# E-39_IPS.net
KiCad netlist of a schematic drawn in Altium Designer
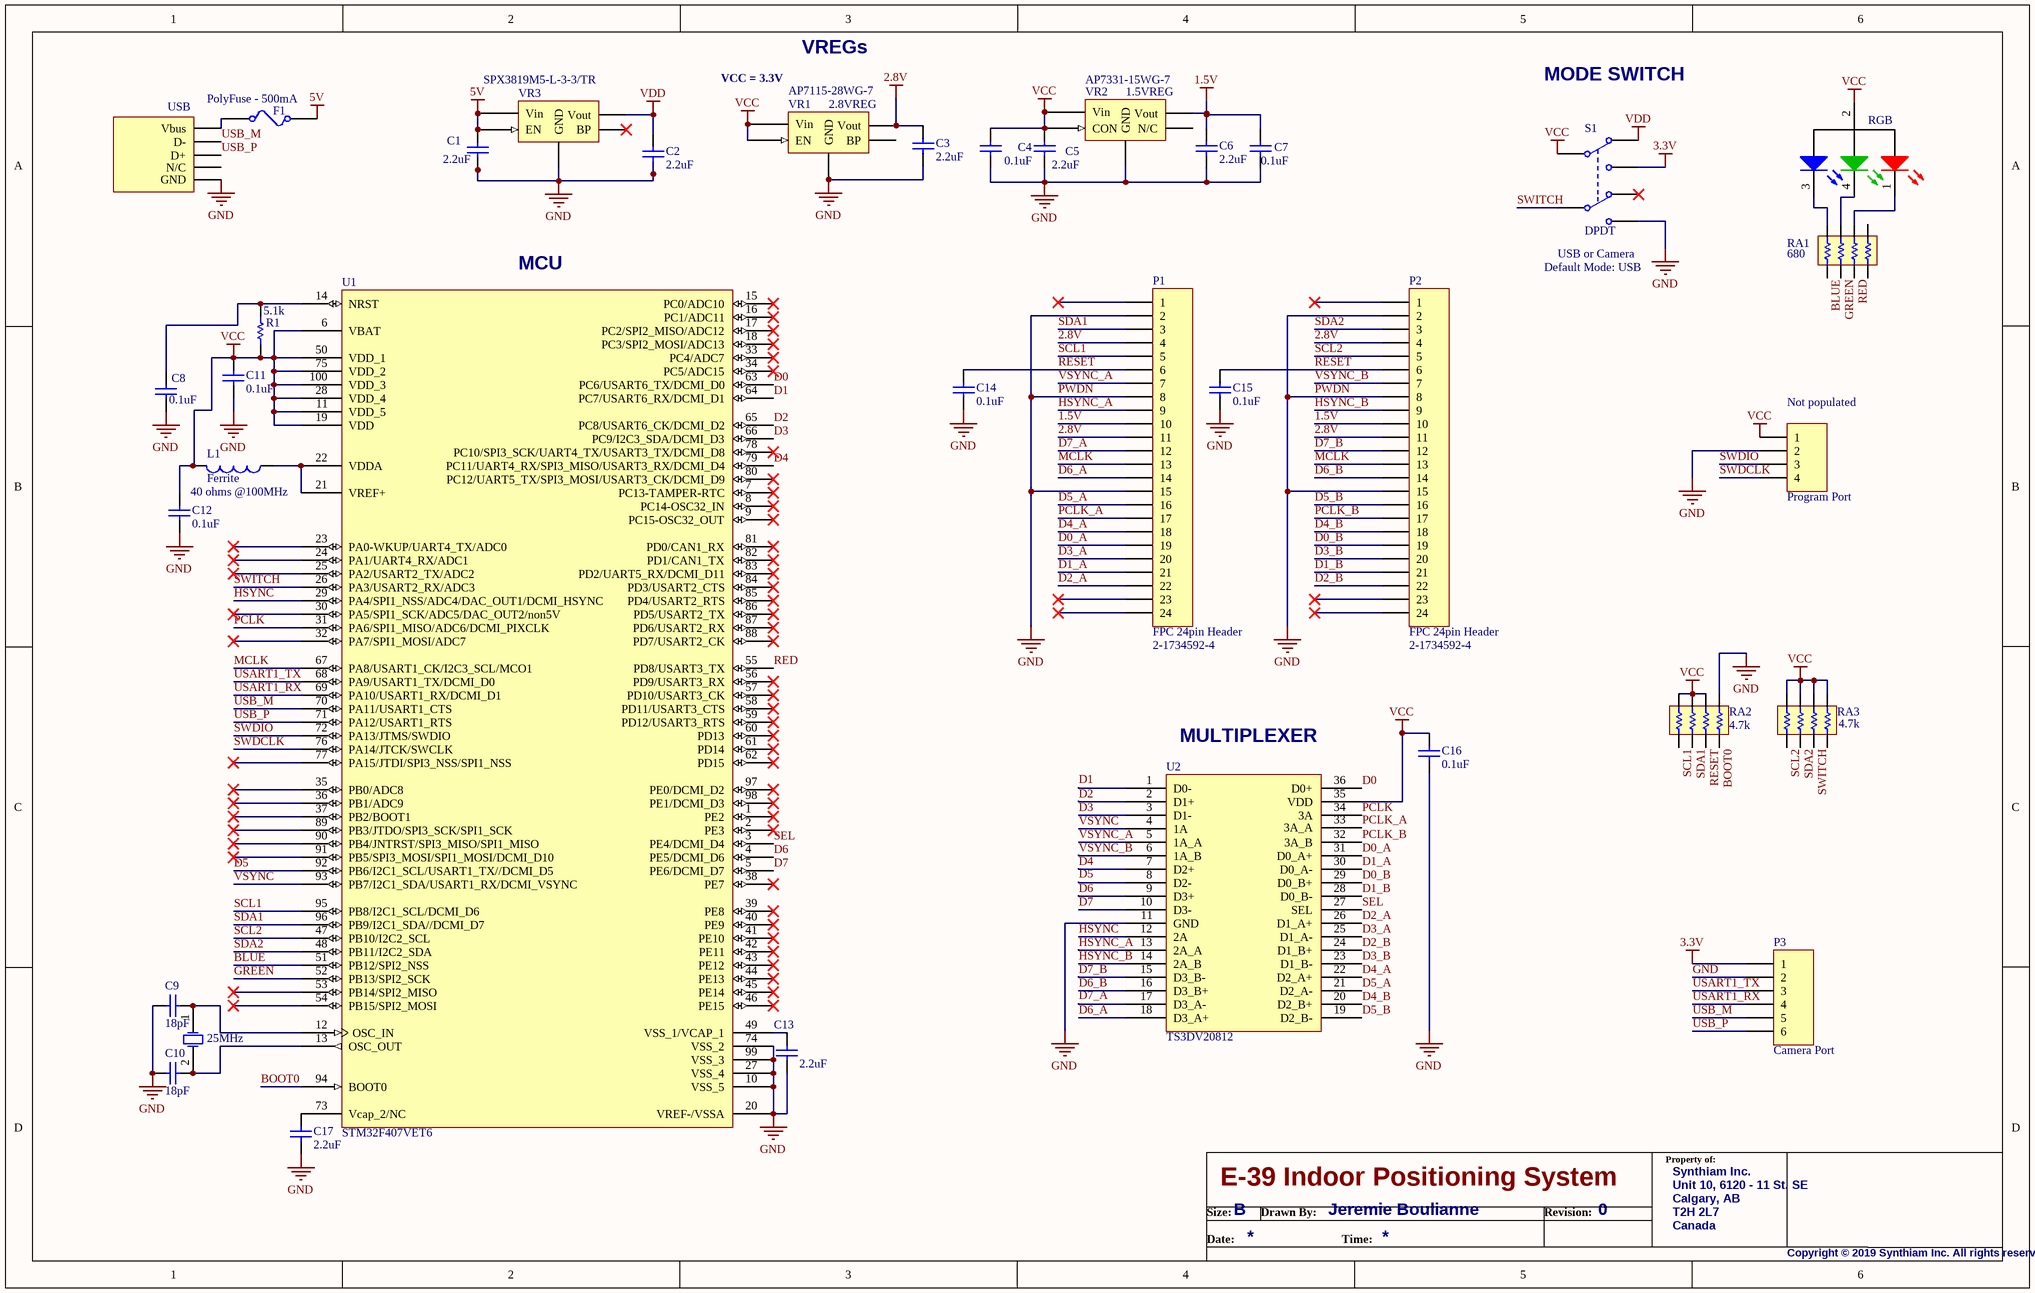
[diagram p0: E-39 IPS.SchDoc]

(export (version "E")
  (design (tool "Eeschema 10.0.6"))
  (components
    (comp (ref "25MHz")
      (value "XTAL 8MHz")
      (footprint "Crystal")
      (description "Crystal Oscillator")
      (fields (field (name "PUBLISHER") "Altium Limited"))
      (libsource (lib "SB_Discrete") (part "XTAL"))
    )
    (comp (ref "C1")
      (value "2.2uF")
      (footprint "0603 TIGHT")
      (description "Capacitor")
      (fields (field (name "Comment") "Cap") (field (name "PUBLISHER") "Altium Limited"))
      (libsource (lib "SB_Discrete") (part "Cap"))
    )
    (comp (ref "C2")
      (value "2.2uF")
      (footprint "0603 TIGHT")
      (description "Capacitor")
      (fields (field (name "Comment") "Cap") (field (name "PUBLISHER") "Altium Limited"))
      (libsource (lib "SB_Discrete") (part "Cap"))
    )
    (comp (ref "C3")
      (value "2.2uF")
      (footprint "0603 TIGHT")
      (description "Capacitor")
      (fields (field (name "PUBLISHER") "Altium Limited"))
      (libsource (lib "SB_Discrete") (part "Cap"))
    )
    (comp (ref "C4")
      (value "0.1uF")
      (footprint "0603 TIGHT")
      (description "Capacitor")
      (fields (field (name "Comment") "2.2uF") (field (name "PUBLISHER") "Altium Limited"))
      (libsource (lib "SB_Discrete") (part "Cap"))
    )
    (comp (ref "C5")
      (value "2.2uF")
      (footprint "0603 TIGHT")
      (description "Capacitor")
      (fields (field (name "PUBLISHER") "Altium Limited"))
      (libsource (lib "SB_Discrete") (part "Cap"))
    )
    (comp (ref "C6")
      (value "2.2uF")
      (footprint "0603 TIGHT")
      (description "Capacitor")
      (fields (field (name "PUBLISHER") "Altium Limited"))
      (libsource (lib "SB_Discrete") (part "Cap"))
    )
    (comp (ref "C7")
      (value "0.1uF")
      (footprint "0603 TIGHT")
      (description "Capacitor")
      (fields (field (name "Comment") "100nF") (field (name "PUBLISHER") "Altium Limited"))
      (libsource (lib "SB_Discrete") (part "Cap"))
    )
    (comp (ref "C8")
      (value "0.1uF")
      (footprint "0603 TIGHT")
      (description "Capacitor")
      (fields (field (name "Comment") "100nF") (field (name "PUBLISHER") "Altium Limited"))
      (libsource (lib "SB_Discrete") (part "Cap"))
    )
    (comp (ref "C9")
      (value "18pF")
      (footprint "0603 TIGHT")
      (description "Capacitor")
      (fields (field (name "PUBLISHER") "Altium Limited"))
      (libsource (lib "SB_Discrete") (part "Cap"))
    )
    (comp (ref "C10")
      (value "18pF")
      (footprint "0603 TIGHT")
      (description "Capacitor")
      (fields (field (name "PUBLISHER") "Altium Limited"))
      (libsource (lib "SB_Discrete") (part "Cap"))
    )
    (comp (ref "C11")
      (value "0.1uF")
      (footprint "0603 TIGHT")
      (description "Capacitor")
      (fields (field (name "Comment") "100nF") (field (name "PUBLISHER") "Altium Limited"))
      (libsource (lib "SB_Discrete") (part "Cap"))
    )
    (comp (ref "C12")
      (value "0.1uF")
      (footprint "0603 TIGHT")
      (description "Capacitor")
      (fields (field (name "Comment") "100nF") (field (name "PUBLISHER") "Altium Limited"))
      (libsource (lib "SB_Discrete") (part "Cap"))
    )
    (comp (ref "C13")
      (value "2.2uF")
      (footprint "0603 TIGHT")
      (description "Capacitor")
      (fields (field (name "PUBLISHER") "Altium Limited"))
      (libsource (lib "SB_Discrete") (part "Cap"))
    )
    (comp (ref "C14")
      (value "0.1uF")
      (footprint "0603 TIGHT")
      (description "Capacitor")
      (fields (field (name "Comment") "18pF") (field (name "PUBLISHER") "Altium Limited"))
      (libsource (lib "SB_Discrete") (part "Cap"))
    )
    (comp (ref "C15")
      (value "0.1uF")
      (footprint "0603 TIGHT")
      (description "Capacitor")
      (fields (field (name "Comment") "18pF") (field (name "PUBLISHER") "Altium Limited"))
      (libsource (lib "SB_Discrete") (part "Cap"))
    )
    (comp (ref "C16")
      (value "0.1uF")
      (footprint "0603 TIGHT")
      (description "Capacitor")
      (fields (field (name "Comment") "18pF") (field (name "PUBLISHER") "Altium Limited"))
      (libsource (lib "SB_Discrete") (part "Cap"))
    )
    (comp (ref "C17")
      (value "2.2uF")
      (footprint "0603 TIGHT")
      (description "Capacitor")
      (fields (field (name "PUBLISHER") "Altium Limited"))
      (libsource (lib "SB_Discrete") (part "Cap"))
    )
    (comp (ref "F1")
      (value "PolyFuse - 500mA")
      (footprint "1206")
      (description "PTC .50A 15VDC RESETTABLE 1812L")
      (libsource (lib "SB_Discrete") (part "PolyFuse"))
    )
    (comp (ref "L1")
      (value "Ferrite")
      (footprint "0603 tight")
      (description "Inductor")
      (fields (field (name "ALTIUM_VALUE") "40 ohms @100MHz") (field (name "PUBLISHER") "Altium Limited"))
      (libsource (lib "Miscellaneous Devices") (part "Inductor"))
    )
    (comp (ref "P1")
      (value "FPC 24pin Header")
      (footprint "FPC Connector 24pin")
      (description "Header, 24-Pin")
      (fields (field (name "PUBLISHER") "Altium Limited"))
      (libsource (lib "Miscellaneous Connectors") (part "Header 24"))
    )
    (comp (ref "P2")
      (value "FPC 24pin Header")
      (footprint "FPC Connector 24pin")
      (description "Header, 24-Pin")
      (fields (field (name "PUBLISHER") "Altium Limited"))
      (libsource (lib "Miscellaneous Connectors") (part "Header 24"))
    )
    (comp (ref "P3")
      (value "Camera Port")
      (footprint "JST-PH 6pin")
      (description "Header, 6-Pin")
      (fields (field (name "PUBLISHER") "Altium Limited"))
      (libsource (lib "Miscellaneous Connectors") (part "Header 6"))
    )
    (comp (ref "Program Port")
      (value "Not populated")
      (footprint "HDR1X4")
      (fields (field (name "PUBLISHER") "Altium Limited"))
      (libsource (lib "Miscellaneous Connectors") (part "Header 4"))
    )
    (comp (ref "R1")
      (value "5.1k")
      (footprint "0603 TIGHT")
      (description "Resistor")
      (fields (field (name "Comment") "Res1") (field (name "PUBLISHER") "Altium Limited"))
      (libsource (lib "SB_Discrete") (part "Res1"))
    )
    (comp (ref "RA1")
      (value "680")
      (footprint "Resistor Array 4")
      (libsource (lib "SB_Discrete") (part "Resistor Array 4"))
    )
    (comp (ref "RA2")
      (value "4.7k")
      (footprint "Resistor Array 4")
      (libsource (lib "SB_Discrete") (part "Resistor Array 4"))
    )
    (comp (ref "RA3")
      (value "4.7k")
      (footprint "Resistor Array 4")
      (libsource (lib "SB_Discrete") (part "Resistor Array 4"))
    )
    (comp (ref "RGB")
      (value "RGBLED-CA")
      (footprint "RGBLED-CA")
      (libsource (lib "SB_Discrete") (part "RGBLED-CA"))
    )
    (comp (ref "S1")
      (value "DPDT")
      (footprint "SWITCH DPDT SMD")
      (libsource (lib "SB_Engineered_Components") (part "SWITCH DPDT"))
    )
    (comp (ref "U1")
      (value "STM32F407VET6")
      (footprint "LQFP100_M")
      (libsource (lib "ST Microcontroller 32-Bit STM32") (part "STM32F2"))
    )
    (comp (ref "U2")
      (value "TS3DV20812")
      (footprint "QFN-36")
      (libsource (lib "SB_Engineered_Components") (part "TS3DV20812"))
    )
    (comp (ref "USB")
      (value "USB Connector")
      (footprint "MICRO USB")
      (libsource (lib "SB_Engineered_Components") (part "USB Connector"))
    )
    (comp (ref "VR1")
      (value "2.8VREG")
      (footprint "SOT-25 New")
      (libsource (lib "SB_Discrete") (part "Vreg SOT25"))
    )
    (comp (ref "VR2") (value "1.5VREG") (footprint "SOT-25 New") (libsource (lib "") (part "Vreg SOT25_1")))
    (comp (ref "VR3")
      (value "SPX3819M5-L-3-3/TR")
      (footprint "SOT-25")
      (libsource (lib "SB_Discrete") (part "Vreg SOT25"))
    )
  )
  (nets
    (net (code "4") (name "/BLUE") (class "Default")
      (node (ref "RA1") (pin "1") (pinfunction "1_1") (pintype "passive"))
      (node (ref "U1") (pin "51") (pinfunction "PB12/SPI2_NSS_51") (pintype "bidirectional"))
    )
    (net (code "5") (name "/BOOT0") (class "Default")
      (node (ref "RA2") (pin "7") (pinfunction "7_7") (pintype "passive"))
      (node (ref "U1") (pin "94") (pinfunction "BOOT0_94") (pintype "input"))
    )
    (net (code "6") (name "/D0") (class "Default")
      (node (ref "U1") (pin "63") (pinfunction "PC6/USART6_TX/DCMI_D0_63") (pintype "bidirectional"))
      (node (ref "U2") (pin "36") (pinfunction "D0+_36") (pintype "passive"))
    )
    (net (code "7") (name "/D0_A") (class "Default")
      (node (ref "P1") (pin "19") (pinfunction "19_19") (pintype "passive"))
      (node (ref "U2") (pin "31") (pinfunction "D0_A+_31") (pintype "passive"))
    )
    (net (code "8") (name "/D0_B") (class "Default")
      (node (ref "P2") (pin "19") (pinfunction "19_19") (pintype "passive"))
      (node (ref "U2") (pin "29") (pinfunction "D0_B+_29") (pintype "passive"))
    )
    (net (code "9") (name "/D1") (class "Default")
      (node (ref "U1") (pin "64") (pinfunction "PC7/USART6_RX/DCMI_D1_64") (pintype "bidirectional"))
      (node (ref "U2") (pin "1") (pinfunction "D0-_1") (pintype "passive"))
    )
    (net (code "10") (name "/D1_A") (class "Default")
      (node (ref "P1") (pin "21") (pinfunction "21_21") (pintype "passive"))
      (node (ref "U2") (pin "30") (pinfunction "D0_A-_30") (pintype "passive"))
    )
    (net (code "11") (name "/D1_B") (class "Default")
      (node (ref "P2") (pin "21") (pinfunction "21_21") (pintype "passive"))
      (node (ref "U2") (pin "28") (pinfunction "D0_B-_28") (pintype "passive"))
    )
    (net (code "12") (name "/D2") (class "Default")
      (node (ref "U1") (pin "65") (pinfunction "PC8/USART6_CK/DCMI_D2_65") (pintype "bidirectional"))
      (node (ref "U2") (pin "2") (pinfunction "D1+_2") (pintype "passive"))
    )
    (net (code "13") (name "/D2_A") (class "Default")
      (node (ref "P1") (pin "22") (pinfunction "22_22") (pintype "passive"))
      (node (ref "U2") (pin "26") (pinfunction "D1_A+_26") (pintype "passive"))
    )
    (net (code "14") (name "/D2_B") (class "Default")
      (node (ref "P2") (pin "22") (pinfunction "22_22") (pintype "passive"))
      (node (ref "U2") (pin "24") (pinfunction "D1_B+_24") (pintype "passive"))
    )
    (net (code "15") (name "/D3") (class "Default")
      (node (ref "U1") (pin "66") (pinfunction "PC9/I2C3_SDA/DCMI_D3_66") (pintype "bidirectional"))
      (node (ref "U2") (pin "3") (pinfunction "D1-_3") (pintype "passive"))
    )
    (net (code "16") (name "/D3_A") (class "Default")
      (node (ref "P1") (pin "20") (pinfunction "20_20") (pintype "passive"))
      (node (ref "U2") (pin "25") (pinfunction "D1_A-_25") (pintype "passive"))
    )
    (net (code "17") (name "/D3_B") (class "Default")
      (node (ref "P2") (pin "20") (pinfunction "20_20") (pintype "passive"))
      (node (ref "U2") (pin "23") (pinfunction "D1_B-_23") (pintype "passive"))
    )
    (net (code "18") (name "/D4") (class "Default")
      (node (ref "U1") (pin "79") (pinfunction "PC11/UART4_RX/SPI3_MISO/USART3_RX/DCMI_D4_79") (pintype "bidirectional"))
      (node (ref "U2") (pin "7") (pinfunction "D2+_7") (pintype "passive"))
    )
    (net (code "19") (name "/D4_A") (class "Default")
      (node (ref "P1") (pin "18") (pinfunction "18_18") (pintype "passive"))
      (node (ref "U2") (pin "22") (pinfunction "D2_A+_22") (pintype "passive"))
    )
    (net (code "20") (name "/D4_B") (class "Default")
      (node (ref "P2") (pin "18") (pinfunction "18_18") (pintype "passive"))
      (node (ref "U2") (pin "20") (pinfunction "D2_B+_20") (pintype "passive"))
    )
    (net (code "21") (name "/D5") (class "Default")
      (node (ref "U1") (pin "92") (pinfunction "PB6/I2C1_SCL/USART1_TX//DCMI_D5_92") (pintype "bidirectional"))
      (node (ref "U2") (pin "8") (pinfunction "D2-_8") (pintype "passive"))
    )
    (net (code "22") (name "/D5_A") (class "Default")
      (node (ref "P1") (pin "16") (pinfunction "16_16") (pintype "passive"))
      (node (ref "U2") (pin "21") (pinfunction "D2_A-_21") (pintype "passive"))
    )
    (net (code "23") (name "/D5_B") (class "Default")
      (node (ref "P2") (pin "16") (pinfunction "16_16") (pintype "passive"))
      (node (ref "U2") (pin "19") (pinfunction "D2_B-_19") (pintype "passive"))
    )
    (net (code "24") (name "/D6") (class "Default")
      (node (ref "U1") (pin "4") (pinfunction "PE5/DCMI_D6_4") (pintype "bidirectional"))
      (node (ref "U2") (pin "9") (pinfunction "D3+_9") (pintype "passive"))
    )
    (net (code "25") (name "/D6_A") (class "Default")
      (node (ref "P1") (pin "14") (pinfunction "14_14") (pintype "passive"))
      (node (ref "U2") (pin "18") (pinfunction "D3_A+_18") (pintype "passive"))
    )
    (net (code "26") (name "/D6_B") (class "Default")
      (node (ref "P2") (pin "14") (pinfunction "14_14") (pintype "passive"))
      (node (ref "U2") (pin "16") (pinfunction "D3_B+_16") (pintype "passive"))
    )
    (net (code "27") (name "/D7") (class "Default")
      (node (ref "U1") (pin "5") (pinfunction "PE6/DCMI_D7_5") (pintype "bidirectional"))
      (node (ref "U2") (pin "10") (pinfunction "D3-_10") (pintype "passive"))
    )
    (net (code "28") (name "/D7_A") (class "Default")
      (node (ref "P1") (pin "12") (pinfunction "12_12") (pintype "passive"))
      (node (ref "U2") (pin "17") (pinfunction "D3_A-_17") (pintype "passive"))
    )
    (net (code "29") (name "/D7_B") (class "Default")
      (node (ref "P2") (pin "12") (pinfunction "12_12") (pintype "passive"))
      (node (ref "U2") (pin "15") (pinfunction "D3_B-_15") (pintype "passive"))
    )
    (net (code "30") (name "/GREEN") (class "Default")
      (node (ref "RA1") (pin "3") (pinfunction "5_3") (pintype "passive"))
      (node (ref "U1") (pin "52") (pinfunction "PB13/SPI2_SCK_52") (pintype "bidirectional"))
    )
    (net (code "31") (name "/HSYNC") (class "Default")
      (node (ref "U1") (pin "29") (pinfunction "PA4/SPI1_NSS/ADC4/DAC_OUT1/DCMI_HSYNC_29") (pintype "bidirectional"))
      (node (ref "U2") (pin "12") (pinfunction "2A_12") (pintype "passive"))
    )
    (net (code "32") (name "/HSYNC_A") (class "Default")
      (node (ref "P1") (pin "9") (pinfunction "9_9") (pintype "passive"))
      (node (ref "U2") (pin "13") (pinfunction "2A_A_13") (pintype "passive"))
    )
    (net (code "33") (name "/HSYNC_B") (class "Default")
      (node (ref "P2") (pin "9") (pinfunction "9_9") (pintype "passive"))
      (node (ref "U2") (pin "14") (pinfunction "2A_B_14") (pintype "passive"))
    )
    (net (code "34") (name "/MCLK") (class "Default")
      (node (ref "P1") (pin "13") (pinfunction "13_13") (pintype "passive"))
      (node (ref "P2") (pin "13") (pinfunction "13_13") (pintype "passive"))
      (node (ref "U1") (pin "67") (pinfunction "PA8/USART1_CK/I2C3_SCL/MCO1_67") (pintype "bidirectional"))
    )
    (net (code "35") (name "/PCLK") (class "Default")
      (node (ref "U1") (pin "31") (pinfunction "PA6/SPI1_MISO/ADC6/DCMI_PIXCLK_31") (pintype "bidirectional"))
      (node (ref "U2") (pin "34") (pinfunction "3A_34") (pintype "passive"))
    )
    (net (code "36") (name "/PCLK_A") (class "Default")
      (node (ref "P1") (pin "17") (pinfunction "17_17") (pintype "passive"))
      (node (ref "U2") (pin "33") (pinfunction "3A_A_33") (pintype "passive"))
    )
    (net (code "37") (name "/PCLK_B") (class "Default")
      (node (ref "P2") (pin "17") (pinfunction "17_17") (pintype "passive"))
      (node (ref "U2") (pin "32") (pinfunction "3A_B_32") (pintype "passive"))
    )
    (net (code "38") (name "/RED") (class "Default")
      (node (ref "RA1") (pin "5") (pinfunction "3_5") (pintype "passive"))
      (node (ref "U1") (pin "55") (pinfunction "PD8/USART3_TX_55") (pintype "bidirectional"))
    )
    (net (code "39") (name "/RESET") (class "Default")
      (node (ref "C14") (pin "2") (pinfunction "2_2") (pintype "passive"))
      (node (ref "C15") (pin "2") (pinfunction "2_2") (pintype "passive"))
      (node (ref "P1") (pin "6") (pinfunction "6_6") (pintype "passive"))
      (node (ref "P2") (pin "6") (pinfunction "6_6") (pintype "passive"))
      (node (ref "RA2") (pin "5") (pinfunction "3_5") (pintype "passive"))
    )
    (net (code "40") (name "/SCL1") (class "Default")
      (node (ref "P1") (pin "5") (pinfunction "5_5") (pintype "passive"))
      (node (ref "RA2") (pin "1") (pinfunction "1_1") (pintype "passive"))
      (node (ref "U1") (pin "95") (pinfunction "PB8/I2C1_SCL/DCMI_D6_95") (pintype "bidirectional"))
    )
    (net (code "41") (name "/SCL2") (class "Default")
      (node (ref "P2") (pin "5") (pinfunction "5_5") (pintype "passive"))
      (node (ref "RA3") (pin "1") (pinfunction "1_1") (pintype "passive"))
      (node (ref "U1") (pin "47") (pinfunction "PB10/I2C2_SCL_47") (pintype "bidirectional"))
    )
    (net (code "42") (name "/SDA1") (class "Default")
      (node (ref "P1") (pin "3") (pinfunction "3_3") (pintype "passive"))
      (node (ref "RA2") (pin "3") (pinfunction "5_3") (pintype "passive"))
      (node (ref "U1") (pin "96") (pinfunction "PB9/I2C1_SDA//DCMI_D7_96") (pintype "bidirectional"))
    )
    (net (code "43") (name "/SDA2") (class "Default")
      (node (ref "P2") (pin "3") (pinfunction "3_3") (pintype "passive"))
      (node (ref "RA3") (pin "3") (pinfunction "5_3") (pintype "passive"))
      (node (ref "U1") (pin "48") (pinfunction "PB11/I2C2_SDA_48") (pintype "bidirectional"))
    )
    (net (code "44") (name "/SEL") (class "Default")
      (node (ref "U1") (pin "3") (pinfunction "PE4/DCMI_D4_3") (pintype "bidirectional"))
      (node (ref "U2") (pin "27") (pinfunction "SEL_27") (pintype "passive"))
    )
    (net (code "45") (name "/SWDCLK") (class "Default")
      (node (ref "Program Port") (pin "4") (pinfunction "4_4") (pintype "passive"))
      (node (ref "U1") (pin "76") (pinfunction "PA14/JTCK/SWCLK_76") (pintype "bidirectional"))
    )
    (net (code "46") (name "/SWDIO") (class "Default")
      (node (ref "Program Port") (pin "3") (pinfunction "3_3") (pintype "passive"))
      (node (ref "U1") (pin "72") (pinfunction "PA13/JTMS/SWDIO_72") (pintype "bidirectional"))
    )
    (net (code "47") (name "/SWITCH") (class "Default")
      (node (ref "RA3") (pin "5") (pinfunction "3_5") (pintype "passive"))
      (node (ref "S1") (pin "5") (pinfunction "COMMON2_5") (pintype "passive"))
      (node (ref "U1") (pin "26") (pinfunction "PA3/USART2_RX/ADC3_26") (pintype "bidirectional"))
    )
    (net (code "48") (name "/USART1_RX") (class "Default")
      (node (ref "P3") (pin "4") (pinfunction "4_4") (pintype "passive"))
      (node (ref "U1") (pin "69") (pinfunction "PA10/USART1_RX/DCMI_D1_69") (pintype "bidirectional"))
    )
    (net (code "49") (name "/USART1_TX") (class "Default")
      (node (ref "P3") (pin "3") (pinfunction "3_3") (pintype "passive"))
      (node (ref "U1") (pin "68") (pinfunction "PA9/USART1_TX/DCMI_D0_68") (pintype "bidirectional"))
    )
    (net (code "50") (name "/USB_M") (class "Default")
      (node (ref "P3") (pin "5") (pinfunction "5_5") (pintype "passive"))
      (node (ref "U1") (pin "70") (pinfunction "PA11/USART1_CTS_70") (pintype "bidirectional"))
      (node (ref "USB") (pin "2") (pinfunction "D-_2") (pintype "passive"))
    )
    (net (code "51") (name "/USB_P") (class "Default")
      (node (ref "P3") (pin "6") (pinfunction "6_6") (pintype "passive"))
      (node (ref "U1") (pin "71") (pinfunction "PA12/USART1_RTS_71") (pintype "bidirectional"))
      (node (ref "USB") (pin "3") (pinfunction "D+_3") (pintype "passive"))
    )
    (net (code "52") (name "/VSYNC") (class "Default")
      (node (ref "U1") (pin "93") (pinfunction "PB7/I2C1_SDA/USART1_RX/DCMI_VSYNC_93") (pintype "bidirectional"))
      (node (ref "U2") (pin "4") (pinfunction "1A_4") (pintype "passive"))
    )
    (net (code "53") (name "/VSYNC_A") (class "Default")
      (node (ref "P1") (pin "7") (pinfunction "7_7") (pintype "passive"))
      (node (ref "U2") (pin "5") (pinfunction "1A_A_5") (pintype "passive"))
    )
    (net (code "54") (name "/VSYNC_B") (class "Default")
      (node (ref "P2") (pin "7") (pinfunction "7_7") (pintype "passive"))
      (node (ref "U2") (pin "6") (pinfunction "1A_B_6") (pintype "passive"))
    )
    (net (code "55") (name "1.5V") (class "Default")
      (node (ref "C6") (pin "1") (pinfunction "1_1") (pintype "passive"))
      (node (ref "C7") (pin "1") (pinfunction "1_1") (pintype "passive"))
      (node (ref "P1") (pin "10") (pinfunction "10_10") (pintype "passive"))
      (node (ref "P2") (pin "10") (pinfunction "10_10") (pintype "passive"))
      (node (ref "VR2") (pin "2") (pinfunction "Vout_2") (pintype "passive"))
    )
    (net (code "56") (name "2.8V") (class "Default")
      (node (ref "C3") (pin "1") (pinfunction "1_1") (pintype "passive"))
      (node (ref "P1") (pin "11") (pinfunction "11_11") (pintype "passive"))
      (node (ref "P1") (pin "4") (pinfunction "4_4") (pintype "passive"))
      (node (ref "P2") (pin "11") (pinfunction "11_11") (pintype "passive"))
      (node (ref "P2") (pin "4") (pinfunction "4_4") (pintype "passive"))
      (node (ref "VR1") (pin "2") (pinfunction "Vout_2") (pintype "passive"))
    )
    (net (code "57") (name "3.3V") (class "Default")
      (node (ref "P3") (pin "1") (pinfunction "1_1") (pintype "passive"))
      (node (ref "S1") (pin "3") (pinfunction "NO1_3") (pintype "passive"))
    )
    (net (code "58") (name "5V") (class "Default")
      (node (ref "C1") (pin "1") (pinfunction "1_1") (pintype "passive"))
      (node (ref "F1") (pin "1") (pinfunction "1_1") (pintype "passive"))
      (node (ref "VR3") (pin "4") (pinfunction "EN_4") (pintype "input"))
      (node (ref "VR3") (pin "5") (pinfunction "Vin_5") (pintype "passive"))
    )
    (net (code "59") (name "GND") (class "Default")
      (node (ref "C1") (pin "2") (pinfunction "2_2") (pintype "passive"))
      (node (ref "C10") (pin "2") (pinfunction "2_2") (pintype "passive"))
      (node (ref "C11") (pin "2") (pinfunction "2_2") (pintype "passive"))
      (node (ref "C12") (pin "1") (pinfunction "1_1") (pintype "passive"))
      (node (ref "C13") (pin "2") (pinfunction "2_2") (pintype "passive"))
      (node (ref "C14") (pin "1") (pinfunction "1_1") (pintype "passive"))
      (node (ref "C15") (pin "1") (pinfunction "1_1") (pintype "passive"))
      (node (ref "C16") (pin "1") (pinfunction "1_1") (pintype "passive"))
      (node (ref "C17") (pin "2") (pinfunction "2_2") (pintype "passive"))
      (node (ref "C2") (pin "2") (pinfunction "2_2") (pintype "passive"))
      (node (ref "C3") (pin "2") (pinfunction "2_2") (pintype "passive"))
      (node (ref "C4") (pin "2") (pinfunction "2_2") (pintype "passive"))
      (node (ref "C5") (pin "2") (pinfunction "2_2") (pintype "passive"))
      (node (ref "C6") (pin "2") (pinfunction "2_2") (pintype "passive"))
      (node (ref "C7") (pin "2") (pinfunction "2_2") (pintype "passive"))
      (node (ref "C8") (pin "2") (pinfunction "2_2") (pintype "passive"))
      (node (ref "C9") (pin "2") (pinfunction "2_2") (pintype "passive"))
      (node (ref "P1") (pin "15") (pinfunction "15_15") (pintype "passive"))
      (node (ref "P1") (pin "2") (pinfunction "2_2") (pintype "passive"))
      (node (ref "P1") (pin "8") (pinfunction "8_8") (pintype "passive"))
      (node (ref "P2") (pin "15") (pinfunction "15_15") (pintype "passive"))
      (node (ref "P2") (pin "2") (pinfunction "2_2") (pintype "passive"))
      (node (ref "P2") (pin "8") (pinfunction "8_8") (pintype "passive"))
      (node (ref "P3") (pin "2") (pinfunction "2_2") (pintype "passive"))
      (node (ref "Program Port") (pin "2") (pinfunction "2_2") (pintype "passive"))
      (node (ref "RA2") (pin "8") (pinfunction "8_8") (pintype "passive"))
      (node (ref "S1") (pin "6") (pinfunction "NO2_6") (pintype "passive"))
      (node (ref "U1") (pin "10") (pinfunction "VSS_5_10") (pintype "power_in"))
      (node (ref "U1") (pin "20") (pinfunction "VREF-/VSSA_20") (pintype "power_in"))
      (node (ref "U1") (pin "27") (pinfunction "VSS_4_27") (pintype "power_in"))
      (node (ref "U1") (pin "74") (pinfunction "VSS_2_74") (pintype "power_in"))
      (node (ref "U1") (pin "99") (pinfunction "VSS_3_99") (pintype "power_in"))
      (node (ref "U2") (pin "11") (pinfunction "GND_11") (pintype "passive"))
      (node (ref "USB") (pin "5") (pinfunction "GND_5") (pintype "passive"))
      (node (ref "VR1") (pin "3") (pinfunction "GND_3") (pintype "passive"))
      (node (ref "VR2") (pin "3") (pinfunction "GND_3") (pintype "passive"))
      (node (ref "VR3") (pin "3") (pinfunction "GND_3") (pintype "passive"))
    )
    (net (code "60") (name "Net-(25MHz-OSC1)") (class "Default")
      (node (ref "25MHz") (pin "1") (pinfunction "OSC1_1") (pintype "passive"))
      (node (ref "C9") (pin "1") (pinfunction "1_1") (pintype "passive"))
      (node (ref "U1") (pin "12") (pinfunction "OSC_IN_12") (pintype "input"))
    )
    (net (code "61") (name "Net-(25MHz-OSC2)") (class "Default")
      (node (ref "25MHz") (pin "2") (pinfunction "OSC2_2") (pintype "passive"))
      (node (ref "C10") (pin "1") (pinfunction "1_1") (pintype "passive"))
      (node (ref "U1") (pin "13") (pinfunction "OSC_OUT_13") (pintype "output"))
    )
    (net (code "62") (name "Net-(RA1-4)") (class "Default")
      (node (ref "RA1") (pin "6") (pinfunction "4_6") (pintype "passive"))
      (node (ref "RGB") (pin "1") (pinfunction "1_1") (pintype "passive"))
    )
    (net (code "63") (name "Net-(RA1-6)") (class "Default")
      (node (ref "RA1") (pin "4") (pinfunction "6_4") (pintype "passive"))
      (node (ref "RGB") (pin "4") (pinfunction "4_4") (pintype "passive"))
    )
    (net (code "64") (name "Net-(RA1-Pad2)") (class "Default")
      (node (ref "RA1") (pin "2") (pinfunction "2_2") (pintype "passive"))
      (node (ref "RGB") (pin "3") (pinfunction "3_3") (pintype "passive"))
    )
    (net (code "65") (name "Net-(U1-NRST)") (class "Default")
      (node (ref "C8") (pin "1") (pinfunction "1_1") (pintype "passive"))
      (node (ref "R1") (pin "1") (pinfunction "1_1") (pintype "passive"))
      (node (ref "U1") (pin "14") (pinfunction "NRST_14") (pintype "bidirectional"))
    )
    (net (code "66") (name "Net-(U1-VDDA)") (class "Default")
      (node (ref "L1") (pin "1") (pinfunction "1_1") (pintype "passive"))
      (node (ref "U1") (pin "21") (pinfunction "VREF+_21") (pintype "power_in"))
      (node (ref "U1") (pin "22") (pinfunction "VDDA_22") (pintype "power_in"))
    )
    (net (code "67") (name "Net-(U1-VSS_1{slash}VCAP_1)") (class "Default")
      (node (ref "C13") (pin "1") (pinfunction "1_1") (pintype "passive"))
      (node (ref "U1") (pin "49") (pinfunction "VSS_1/VCAP_1_49") (pintype "power_in"))
    )
    (net (code "68") (name "Net-(U1-Vcap_2{slash}NC)") (class "Default")
      (node (ref "C17") (pin "1") (pinfunction "1_1") (pintype "passive"))
      (node (ref "U1") (pin "73") (pinfunction "Vcap_2/NC_73") (pintype "passive"))
    )
    (net (code "69") (name "Net-(USB-Vbus)") (class "Default")
      (node (ref "F1") (pin "2") (pinfunction "2_2") (pintype "passive"))
      (node (ref "USB") (pin "1") (pinfunction "Vbus_1") (pintype "passive"))
    )
    (net (code "70") (name "VCC") (class "Default")
      (node (ref "C11") (pin "1") (pinfunction "1_1") (pintype "passive"))
      (node (ref "C12") (pin "2") (pinfunction "2_2") (pintype "passive"))
      (node (ref "C16") (pin "2") (pinfunction "2_2") (pintype "passive"))
      (node (ref "C4") (pin "1") (pinfunction "1_1") (pintype "passive"))
      (node (ref "C5") (pin "1") (pinfunction "1_1") (pintype "passive"))
      (node (ref "L1") (pin "2") (pinfunction "2_2") (pintype "passive"))
      (node (ref "Program Port") (pin "1") (pinfunction "1_1") (pintype "passive"))
      (node (ref "R1") (pin "2") (pinfunction "2_2") (pintype "passive"))
      (node (ref "RA2") (pin "2") (pinfunction "2_2") (pintype "passive"))
      (node (ref "RA2") (pin "4") (pinfunction "6_4") (pintype "passive"))
      (node (ref "RA2") (pin "6") (pinfunction "4_6") (pintype "passive"))
      (node (ref "RA3") (pin "2") (pinfunction "2_2") (pintype "passive"))
      (node (ref "RA3") (pin "4") (pinfunction "6_4") (pintype "passive"))
      (node (ref "RA3") (pin "6") (pinfunction "4_6") (pintype "passive"))
      (node (ref "RA3") (pin "8") (pinfunction "8_8") (pintype "passive"))
      (node (ref "RGB") (pin "2") (pinfunction "2_2") (pintype "passive"))
      (node (ref "S1") (pin "2") (pinfunction "COMMON1_2") (pintype "passive"))
      (node (ref "U1") (pin "100") (pinfunction "VDD_3_100") (pintype "power_in"))
      (node (ref "U1") (pin "11") (pinfunction "VDD_5_11") (pintype "power_in"))
      (node (ref "U1") (pin "19") (pinfunction "VDD_19") (pintype "power_in"))
      (node (ref "U1") (pin "28") (pinfunction "VDD_4_28") (pintype "power_in"))
      (node (ref "U1") (pin "50") (pinfunction "VDD_1_50") (pintype "power_in"))
      (node (ref "U1") (pin "6") (pinfunction "VBAT_6") (pintype "power_in"))
      (node (ref "U1") (pin "75") (pinfunction "VDD_2_75") (pintype "power_in"))
      (node (ref "U2") (pin "35") (pinfunction "VDD_35") (pintype "passive"))
      (node (ref "VR1") (pin "4") (pinfunction "EN_4") (pintype "input"))
      (node (ref "VR1") (pin "5") (pinfunction "Vin_5") (pintype "passive"))
      (node (ref "VR2") (pin "4") (pinfunction "CON_4") (pintype "input"))
      (node (ref "VR2") (pin "5") (pinfunction "Vin_5") (pintype "passive"))
    )
    (net (code "71") (name "VDD") (class "Default")
      (node (ref "C2") (pin "1") (pinfunction "1_1") (pintype "passive"))
      (node (ref "S1") (pin "1") (pinfunction "NC1_1") (pintype "passive"))
      (node (ref "VR3") (pin "2") (pinfunction "Vout_2") (pintype "passive"))
    )
    (net (code "72") (name "unconnected-(P1-Pad1)") (class "Default")
      (node (ref "P1") (pin "1") (pinfunction "1_1") (pintype "passive+no_connect"))
    )
    (net (code "73") (name "unconnected-(P1-Pad23)") (class "Default")
      (node (ref "P1") (pin "23") (pinfunction "23_23") (pintype "passive+no_connect"))
    )
    (net (code "74") (name "unconnected-(P1-Pad24)") (class "Default")
      (node (ref "P1") (pin "24") (pinfunction "24_24") (pintype "passive+no_connect"))
    )
    (net (code "75") (name "unconnected-(P2-Pad1)") (class "Default")
      (node (ref "P2") (pin "1") (pinfunction "1_1") (pintype "passive+no_connect"))
    )
    (net (code "76") (name "unconnected-(P2-Pad23)") (class "Default")
      (node (ref "P2") (pin "23") (pinfunction "23_23") (pintype "passive+no_connect"))
    )
    (net (code "77") (name "unconnected-(P2-Pad24)") (class "Default")
      (node (ref "P2") (pin "24") (pinfunction "24_24") (pintype "passive+no_connect"))
    )
    (net (code "78") (name "unconnected-(RA1-Pad7)") (class "Default")
      (node (ref "RA1") (pin "7") (pinfunction "7_7") (pintype "passive"))
    )
    (net (code "79") (name "unconnected-(RA1-Pad8)") (class "Default")
      (node (ref "RA1") (pin "8") (pinfunction "8_8") (pintype "passive"))
    )
    (net (code "80") (name "unconnected-(RA3-Pad7)") (class "Default")
      (node (ref "RA3") (pin "7") (pinfunction "7_7") (pintype "passive"))
    )
    (net (code "81") (name "unconnected-(RGB-A-Pad1)") (class "Default")
      (node (ref "RGB") (pin "1") (pinfunction "A_1") (pintype "passive"))
    )
    (net (code "82") (name "unconnected-(RGB-A-Pad1)_1") (class "Default")
      (node (ref "RGB") (pin "1") (pinfunction "A_1") (pintype "passive"))
    )
    (net (code "83") (name "unconnected-(RGB-A-Pad1)_2") (class "Default")
      (node (ref "RGB") (pin "1") (pinfunction "A_1") (pintype "passive"))
    )
    (net (code "84") (name "unconnected-(S1-NC2-Pad4)") (class "Default")
      (node (ref "S1") (pin "4") (pinfunction "NC2_4") (pintype "passive+no_connect"))
    )
    (net (code "85") (name "unconnected-(U1-PA0-WKUP{slash}UART4_TX{slash}ADC0-Pad23)") (class "Default")
      (node (ref "U1") (pin "23") (pinfunction "PA0-WKUP/UART4_TX/ADC0_23") (pintype "bidirectional+no_connect"))
    )
    (net (code "86") (name "unconnected-(U1-PA1{slash}UART4_RX{slash}ADC1-Pad24)") (class "Default")
      (node (ref "U1") (pin "24") (pinfunction "PA1/UART4_RX/ADC1_24") (pintype "bidirectional+no_connect"))
    )
    (net (code "87") (name "unconnected-(U1-PA2{slash}USART2_TX{slash}ADC2-Pad25)") (class "Default")
      (node (ref "U1") (pin "25") (pinfunction "PA2/USART2_TX/ADC2_25") (pintype "bidirectional+no_connect"))
    )
    (net (code "88") (name "unconnected-(U1-PA5{slash}SPI1_SCK{slash}ADC5{slash}DAC_OUT2{slash}non5V-Pad30)") (class "Default")
      (node (ref "U1") (pin "30") (pinfunction "PA5/SPI1_SCK/ADC5/DAC_OUT2/non5V_30") (pintype "bidirectional+no_connect"))
    )
    (net (code "89") (name "unconnected-(U1-PA7{slash}SPI1_MOSI{slash}ADC7-Pad32)") (class "Default")
      (node (ref "U1") (pin "32") (pinfunction "PA7/SPI1_MOSI/ADC7_32") (pintype "bidirectional+no_connect"))
    )
    (net (code "90") (name "unconnected-(U1-PA15{slash}JTDI{slash}SPI3_NSS{slash}SPI1_NSS-Pad77)") (class "Default")
      (node (ref "U1") (pin "77") (pinfunction "PA15/JTDI/SPI3_NSS/SPI1_NSS_77") (pintype "bidirectional+no_connect"))
    )
    (net (code "91") (name "unconnected-(U1-PB0{slash}ADC8-Pad35)") (class "Default")
      (node (ref "U1") (pin "35") (pinfunction "PB0/ADC8_35") (pintype "bidirectional+no_connect"))
    )
    (net (code "92") (name "unconnected-(U1-PB1{slash}ADC9-Pad36)") (class "Default")
      (node (ref "U1") (pin "36") (pinfunction "PB1/ADC9_36") (pintype "bidirectional+no_connect"))
    )
    (net (code "93") (name "unconnected-(U1-PB2{slash}BOOT1-Pad37)") (class "Default")
      (node (ref "U1") (pin "37") (pinfunction "PB2/BOOT1_37") (pintype "bidirectional+no_connect"))
    )
    (net (code "94") (name "unconnected-(U1-PB3{slash}JTDO{slash}SPI3_SCK{slash}SPI1_SCK-Pad89)") (class "Default")
      (node (ref "U1") (pin "89") (pinfunction "PB3/JTDO/SPI3_SCK/SPI1_SCK_89") (pintype "bidirectional+no_connect"))
    )
    (net (code "95") (name "unconnected-(U1-PB4{slash}JNTRST{slash}SPI3_MISO{slash}SPI1_MISO-Pad90)") (class "Default")
      (node (ref "U1") (pin "90") (pinfunction "PB4/JNTRST/SPI3_MISO/SPI1_MISO_90") (pintype "bidirectional+no_connect"))
    )
    (net (code "96") (name "unconnected-(U1-PB5{slash}SPI3_MOSI{slash}SPI1_MOSI{slash}DCMI_D10-Pad91)") (class "Default")
      (node (ref "U1") (pin "91") (pinfunction "PB5/SPI3_MOSI/SPI1_MOSI/DCMI_D10_91") (pintype "bidirectional+no_connect"))
    )
    (net (code "97") (name "unconnected-(U1-PB14{slash}SPI2_MISO-Pad53)") (class "Default")
      (node (ref "U1") (pin "53") (pinfunction "PB14/SPI2_MISO_53") (pintype "bidirectional+no_connect"))
    )
    (net (code "98") (name "unconnected-(U1-PB15{slash}SPI2_MOSI-Pad54)") (class "Default")
      (node (ref "U1") (pin "54") (pinfunction "PB15/SPI2_MOSI_54") (pintype "bidirectional+no_connect"))
    )
    (net (code "99") (name "unconnected-(U1-PC0{slash}ADC10-Pad15)") (class "Default")
      (node (ref "U1") (pin "15") (pinfunction "PC0/ADC10_15") (pintype "bidirectional+no_connect"))
    )
    (net (code "100") (name "unconnected-(U1-PC1{slash}ADC11-Pad16)") (class "Default")
      (node (ref "U1") (pin "16") (pinfunction "PC1/ADC11_16") (pintype "bidirectional+no_connect"))
    )
    (net (code "101") (name "unconnected-(U1-PC2{slash}SPI2_MISO{slash}ADC12-Pad17)") (class "Default")
      (node (ref "U1") (pin "17") (pinfunction "PC2/SPI2_MISO/ADC12_17") (pintype "bidirectional+no_connect"))
    )
    (net (code "102") (name "unconnected-(U1-PC3{slash}SPI2_MOSI{slash}ADC13-Pad18)") (class "Default")
      (node (ref "U1") (pin "18") (pinfunction "PC3/SPI2_MOSI/ADC13_18") (pintype "bidirectional+no_connect"))
    )
    (net (code "103") (name "unconnected-(U1-PC4{slash}ADC7-Pad33)") (class "Default")
      (node (ref "U1") (pin "33") (pinfunction "PC4/ADC7_33") (pintype "bidirectional+no_connect"))
    )
    (net (code "104") (name "unconnected-(U1-PC5{slash}ADC15-Pad34)") (class "Default")
      (node (ref "U1") (pin "34") (pinfunction "PC5/ADC15_34") (pintype "bidirectional+no_connect"))
    )
    (net (code "105") (name "unconnected-(U1-PC10{slash}SPI3_SCK{slash}UART4_TX{slash}USART3_TX{slash}DCMI_D8-Pad78)") (class "Default")
      (node (ref "U1") (pin "78") (pinfunction "PC10/SPI3_SCK/UART4_TX/USART3_TX/DCMI_D8_78") (pintype "bidirectional+no_connect"))
    )
    (net (code "106") (name "unconnected-(U1-PC12{slash}UART5_TX{slash}SPI3_MOSI{slash}USART3_CK{slash}DCMI_D9-Pad80)") (class "Default")
      (node (ref "U1") (pin "80") (pinfunction "PC12/UART5_TX/SPI3_MOSI/USART3_CK/DCMI_D9_80") (pintype "bidirectional+no_connect"))
    )
    (net (code "107") (name "unconnected-(U1-PC13-TAMPER-RTC-Pad7)") (class "Default")
      (node (ref "U1") (pin "7") (pinfunction "PC13-TAMPER-RTC_7") (pintype "bidirectional+no_connect"))
    )
    (net (code "108") (name "unconnected-(U1-PC14-OSC32_IN-Pad8)") (class "Default")
      (node (ref "U1") (pin "8") (pinfunction "PC14-OSC32_IN_8") (pintype "bidirectional+no_connect"))
    )
    (net (code "109") (name "unconnected-(U1-PC15-OSC32_OUT-Pad9)") (class "Default")
      (node (ref "U1") (pin "9") (pinfunction "PC15-OSC32_OUT_9") (pintype "bidirectional+no_connect"))
    )
    (net (code "110") (name "unconnected-(U1-PD0{slash}CAN1_RX-Pad81)") (class "Default")
      (node (ref "U1") (pin "81") (pinfunction "PD0/CAN1_RX_81") (pintype "bidirectional+no_connect"))
    )
    (net (code "111") (name "unconnected-(U1-PD1{slash}CAN1_TX-Pad82)") (class "Default")
      (node (ref "U1") (pin "82") (pinfunction "PD1/CAN1_TX_82") (pintype "bidirectional+no_connect"))
    )
    (net (code "112") (name "unconnected-(U1-PD2{slash}UART5_RX{slash}DCMI_D11-Pad83)") (class "Default")
      (node (ref "U1") (pin "83") (pinfunction "PD2/UART5_RX/DCMI_D11_83") (pintype "bidirectional+no_connect"))
    )
    (net (code "113") (name "unconnected-(U1-PD3{slash}USART2_CTS-Pad84)") (class "Default")
      (node (ref "U1") (pin "84") (pinfunction "PD3/USART2_CTS_84") (pintype "bidirectional+no_connect"))
    )
    (net (code "114") (name "unconnected-(U1-PD4{slash}USART2_RTS-Pad85)") (class "Default")
      (node (ref "U1") (pin "85") (pinfunction "PD4/USART2_RTS_85") (pintype "bidirectional+no_connect"))
    )
    (net (code "115") (name "unconnected-(U1-PD5{slash}USART2_TX-Pad86)") (class "Default")
      (node (ref "U1") (pin "86") (pinfunction "PD5/USART2_TX_86") (pintype "bidirectional+no_connect"))
    )
    (net (code "116") (name "unconnected-(U1-PD6{slash}USART2_RX-Pad87)") (class "Default")
      (node (ref "U1") (pin "87") (pinfunction "PD6/USART2_RX_87") (pintype "bidirectional+no_connect"))
    )
    (net (code "117") (name "unconnected-(U1-PD7{slash}USART2_CK-Pad88)") (class "Default")
      (node (ref "U1") (pin "88") (pinfunction "PD7/USART2_CK_88") (pintype "bidirectional+no_connect"))
    )
    (net (code "118") (name "unconnected-(U1-PD9{slash}USART3_RX-Pad56)") (class "Default")
      (node (ref "U1") (pin "56") (pinfunction "PD9/USART3_RX_56") (pintype "bidirectional+no_connect"))
    )
    (net (code "119") (name "unconnected-(U1-PD10{slash}USART3_CK-Pad57)") (class "Default")
      (node (ref "U1") (pin "57") (pinfunction "PD10/USART3_CK_57") (pintype "bidirectional+no_connect"))
    )
    (net (code "120") (name "unconnected-(U1-PD11{slash}USART3_CTS-Pad58)") (class "Default")
      (node (ref "U1") (pin "58") (pinfunction "PD11/USART3_CTS_58") (pintype "bidirectional+no_connect"))
    )
    (net (code "121") (name "unconnected-(U1-PD12{slash}USART3_RTS-Pad59)") (class "Default")
      (node (ref "U1") (pin "59") (pinfunction "PD12/USART3_RTS_59") (pintype "bidirectional+no_connect"))
    )
    (net (code "122") (name "unconnected-(U1-PD13-Pad60)") (class "Default")
      (node (ref "U1") (pin "60") (pinfunction "PD13_60") (pintype "bidirectional+no_connect"))
    )
    (net (code "123") (name "unconnected-(U1-PD14-Pad61)") (class "Default")
      (node (ref "U1") (pin "61") (pinfunction "PD14_61") (pintype "bidirectional+no_connect"))
    )
    (net (code "124") (name "unconnected-(U1-PD15-Pad62)") (class "Default")
      (node (ref "U1") (pin "62") (pinfunction "PD15_62") (pintype "bidirectional+no_connect"))
    )
    (net (code "125") (name "unconnected-(U1-PE0{slash}DCMI_D2-Pad97)") (class "Default")
      (node (ref "U1") (pin "97") (pinfunction "PE0/DCMI_D2_97") (pintype "bidirectional+no_connect"))
    )
    (net (code "126") (name "unconnected-(U1-PE1{slash}DCMI_D3-Pad98)") (class "Default")
      (node (ref "U1") (pin "98") (pinfunction "PE1/DCMI_D3_98") (pintype "bidirectional+no_connect"))
    )
    (net (code "127") (name "unconnected-(U1-PE2-Pad1)") (class "Default")
      (node (ref "U1") (pin "1") (pinfunction "PE2_1") (pintype "bidirectional+no_connect"))
    )
    (net (code "128") (name "unconnected-(U1-PE3-Pad2)") (class "Default")
      (node (ref "U1") (pin "2") (pinfunction "PE3_2") (pintype "bidirectional+no_connect"))
    )
    (net (code "129") (name "unconnected-(U1-PE7-Pad38)") (class "Default")
      (node (ref "U1") (pin "38") (pinfunction "PE7_38") (pintype "bidirectional+no_connect"))
    )
    (net (code "130") (name "unconnected-(U1-PE8-Pad39)") (class "Default")
      (node (ref "U1") (pin "39") (pinfunction "PE8_39") (pintype "bidirectional+no_connect"))
    )
    (net (code "131") (name "unconnected-(U1-PE9-Pad40)") (class "Default")
      (node (ref "U1") (pin "40") (pinfunction "PE9_40") (pintype "bidirectional+no_connect"))
    )
    (net (code "132") (name "unconnected-(U1-PE10-Pad41)") (class "Default")
      (node (ref "U1") (pin "41") (pinfunction "PE10_41") (pintype "bidirectional+no_connect"))
    )
    (net (code "133") (name "unconnected-(U1-PE11-Pad42)") (class "Default")
      (node (ref "U1") (pin "42") (pinfunction "PE11_42") (pintype "bidirectional+no_connect"))
    )
    (net (code "134") (name "unconnected-(U1-PE12-Pad43)") (class "Default")
      (node (ref "U1") (pin "43") (pinfunction "PE12_43") (pintype "bidirectional+no_connect"))
    )
    (net (code "135") (name "unconnected-(U1-PE13-Pad44)") (class "Default")
      (node (ref "U1") (pin "44") (pinfunction "PE13_44") (pintype "bidirectional+no_connect"))
    )
    (net (code "136") (name "unconnected-(U1-PE14-Pad45)") (class "Default")
      (node (ref "U1") (pin "45") (pinfunction "PE14_45") (pintype "bidirectional+no_connect"))
    )
    (net (code "137") (name "unconnected-(U1-PE15-Pad46)") (class "Default")
      (node (ref "U1") (pin "46") (pinfunction "PE15_46") (pintype "bidirectional+no_connect"))
    )
    (net (code "138") (name "unconnected-(USB-N{slash}C-Pad4)") (class "Default")
      (node (ref "USB") (pin "4") (pinfunction "N/C_4") (pintype "passive"))
    )
    (net (code "139") (name "unconnected-(VR1-BP-Pad1)") (class "Default")
      (node (ref "VR1") (pin "1") (pinfunction "BP_1") (pintype "passive"))
    )
    (net (code "140") (name "unconnected-(VR2-N{slash}C-Pad1)") (class "Default")
      (node (ref "VR2") (pin "1") (pinfunction "N/C_1") (pintype "passive"))
    )
    (net (code "141") (name "unconnected-(VR3-BP-Pad1)") (class "Default")
      (node (ref "VR3") (pin "1") (pinfunction "BP_1") (pintype "passive+no_connect"))
    )
  )
)
